# sx-fundec45-rev3.net
KiCad netlist of a schematic drawn in EAGLE
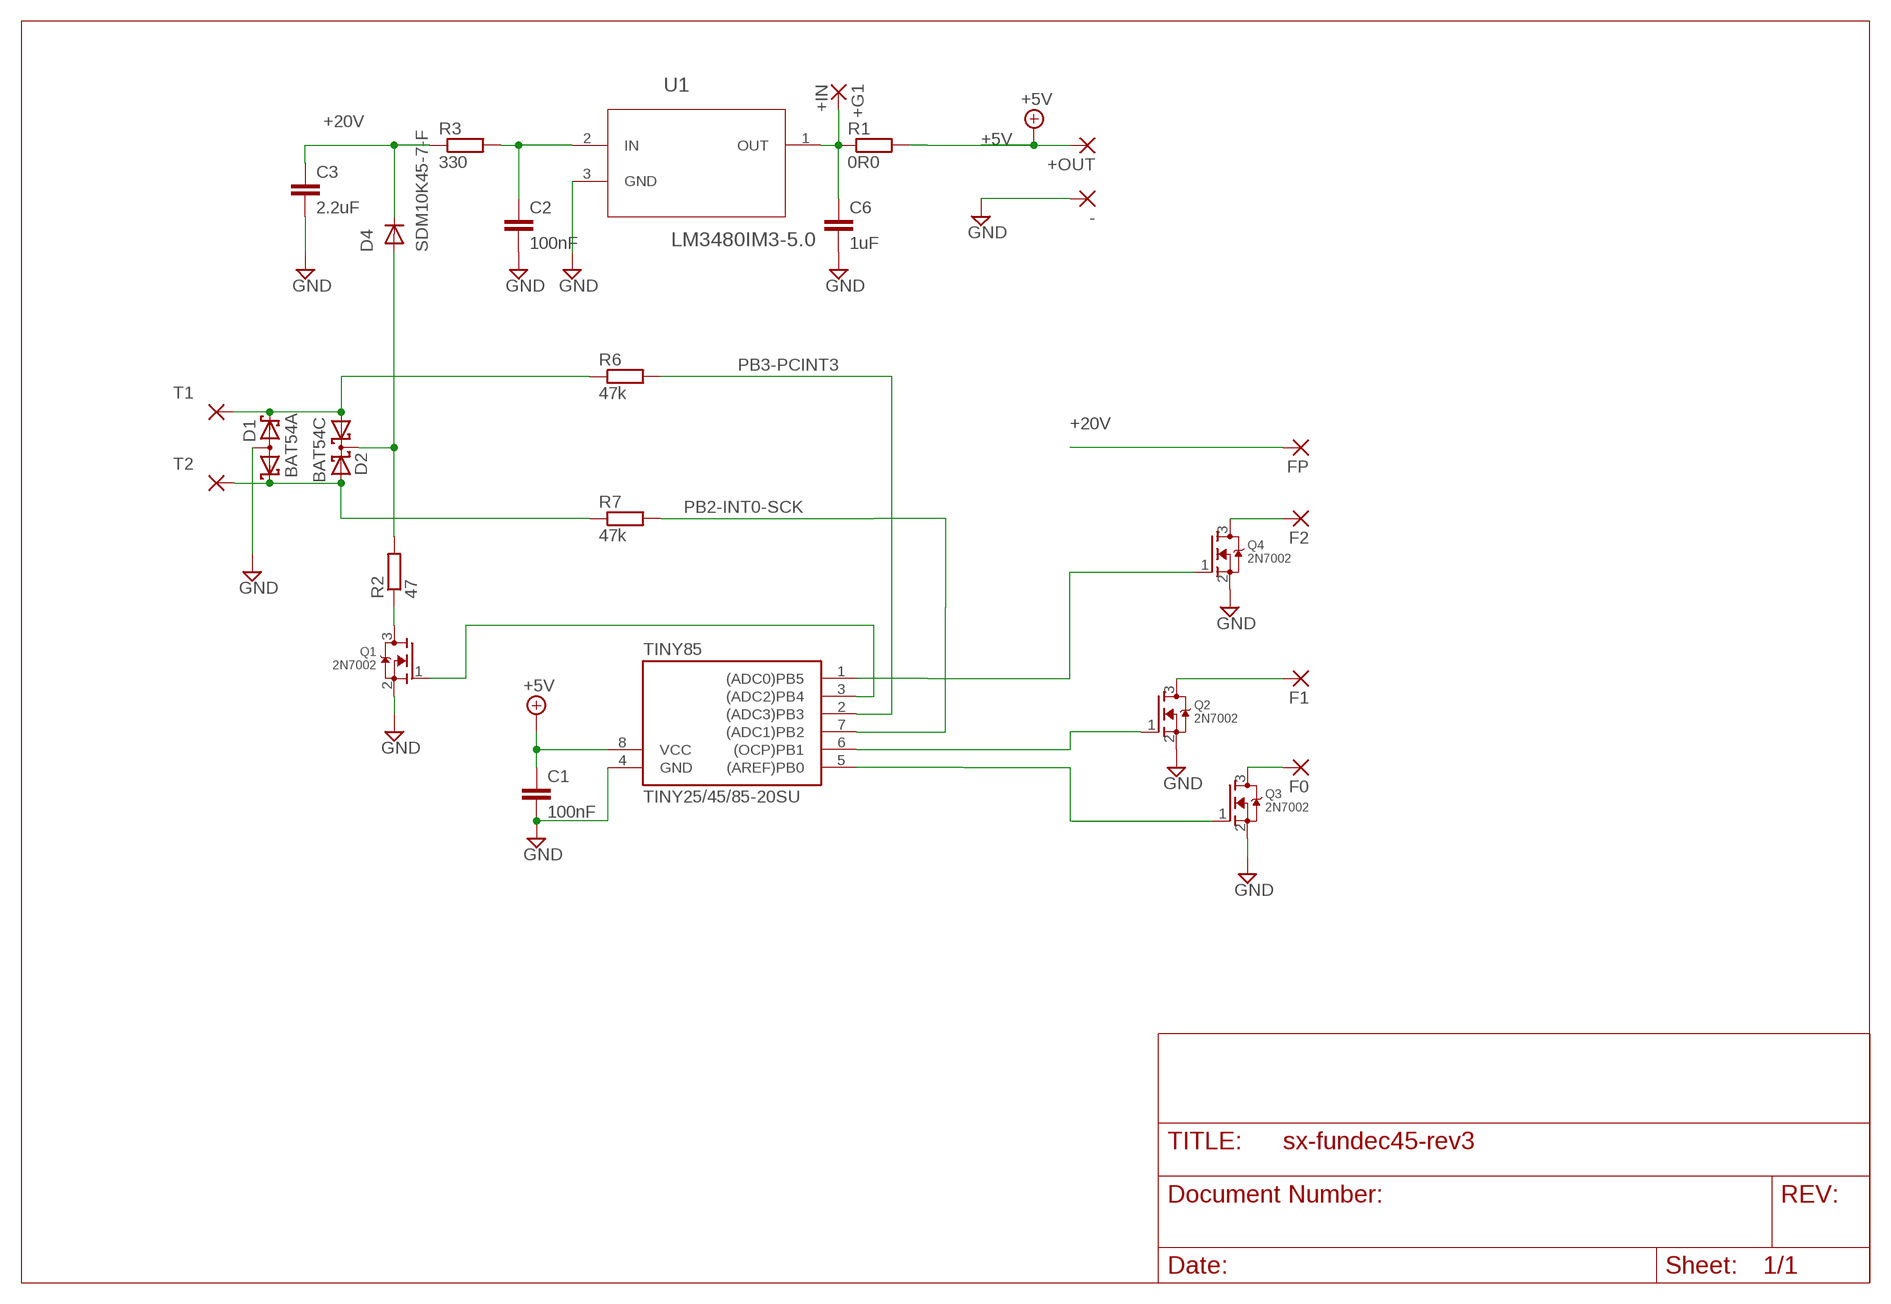
[diagram p0: schematic, sheet 1]

(export (version "E")
  (design (tool "Eeschema 10.0.6"))
  (components
    (comp (ref "+G1")
      (value "+IN")
      (footprint "eagle-import:SMD1,27-2,54")
      (libsource (lib "eagle-import") (part "SMD2"))
    )
    (comp (ref "+OUT")
      (value "SMD2")
      (footprint "eagle-import:SMD1,27-2,54")
      (libsource (lib "eagle-import") (part "SMD2"))
    )
    (comp (ref "-")
      (value "SMD2")
      (footprint "eagle-import:SMD1,27-2,54")
      (libsource (lib "eagle-import") (part "SMD2"))
    )
    (comp (ref "C1")
      (value "100nF")
      (footprint "eagle-import:C0805")
      (libsource (lib "eagle-import") (part "C-EUC0805"))
    )
    (comp (ref "C2")
      (value "100nF")
      (footprint "eagle-import:C0805")
      (libsource (lib "eagle-import") (part "C-EUC0805"))
    )
    (comp (ref "C3")
      (value "2.2uF")
      (footprint "eagle-import:C1206")
      (libsource (lib "eagle-import") (part "C-EUC1206"))
    )
    (comp (ref "C6")
      (value "1uF")
      (footprint "eagle-import:C0805")
      (libsource (lib "eagle-import") (part "C-EUC0805"))
    )
    (comp (ref "D1")
      (value "BAT54A")
      (footprint "eagle-import:SOT23")
      (libsource (lib "eagle-import") (part "BAT54A"))
    )
    (comp (ref "D2")
      (value "BAT54C")
      (footprint "eagle-import:SOT23")
      (libsource (lib "eagle-import") (part "BAT54C"))
    )
    (comp (ref "D4")
      (value "SDM10K45-7-F")
      (footprint "eagle-import:SOD323-R")
      (libsource (lib "eagle-import") (part "DIODE-SOD323-R"))
    )
    (comp (ref "F0")
      (value "SMD2")
      (footprint "eagle-import:SMD1,27-2,54")
      (libsource (lib "eagle-import") (part "SMD2"))
    )
    (comp (ref "F1")
      (value "SMD2")
      (footprint "eagle-import:SMD1,27-2,54")
      (libsource (lib "eagle-import") (part "SMD2"))
    )
    (comp (ref "F2")
      (value "SMD2")
      (footprint "eagle-import:SMD1,27-2,54")
      (libsource (lib "eagle-import") (part "SMD2"))
    )
    (comp (ref "FP")
      (value "SMD2")
      (footprint "eagle-import:SMD1,27-2,54")
      (libsource (lib "eagle-import") (part "SMD2"))
    )
    (comp (ref "Q1")
      (value "2N7002")
      (footprint "eagle-import:SOT23")
      (libsource (lib "eagle-import") (part "MOSFET-NREFLOW"))
    )
    (comp (ref "Q2")
      (value "2N7002")
      (footprint "eagle-import:SOT23")
      (libsource (lib "eagle-import") (part "MOSFET-NREFLOW"))
    )
    (comp (ref "Q3")
      (value "2N7002")
      (footprint "eagle-import:SOT23")
      (libsource (lib "eagle-import") (part "MOSFET-NREFLOW"))
    )
    (comp (ref "Q4")
      (value "2N7002")
      (footprint "eagle-import:SOT23")
      (libsource (lib "eagle-import") (part "MOSFET-NREFLOW"))
    )
    (comp (ref "R1")
      (value "0R0")
      (footprint "eagle-import:M0805")
      (libsource (lib "eagle-import") (part "R-EU_M0805"))
    )
    (comp (ref "R2")
      (value "47")
      (footprint "eagle-import:R0805")
      (libsource (lib "eagle-import") (part "R-EU_R0805"))
    )
    (comp (ref "R3")
      (value "330")
      (footprint "eagle-import:M0805")
      (libsource (lib "eagle-import") (part "R-EU_M0805"))
    )
    (comp (ref "R6")
      (value "47k")
      (footprint "eagle-import:R0805")
      (libsource (lib "eagle-import") (part "R-EU_R0805"))
    )
    (comp (ref "R7")
      (value "47k")
      (footprint "eagle-import:M0805")
      (libsource (lib "eagle-import") (part "R-EU_M0805"))
    )
    (comp (ref "T1")
      (value "SMD2")
      (footprint "eagle-import:SMD1,27-2,54")
      (libsource (lib "eagle-import") (part "SMD2"))
    )
    (comp (ref "T2")
      (value "SMD2")
      (footprint "eagle-import:SMD1,27-2,54")
      (libsource (lib "eagle-import") (part "SMD2"))
    )
    (comp (ref "TINY85")
      (value "TINY25/45/85-20SU")
      (footprint "eagle-import:SOIC8")
      (libsource (lib "eagle-import") (part "TINY25/45/85-20SU"))
    )
    (comp (ref "U1")
      (value "LM3480IM3-5.0")
      (footprint "eagle-import:SOT95P263X110-3N")
      (fields (field (name "MPN") "LM3480IM3-50"))
      (libsource (lib "eagle-import") (part "LM3480IM3-5.0"))
    )
  )
  (nets
    (net (code "1") (name "+5V") (class "Default")
      (node (ref "+OUT") (pin "1") (pinfunction "P_1") (pintype "passive"))
      (node (ref "C1") (pin "1") (pinfunction "1_1") (pintype "passive"))
      (node (ref "R1") (pin "2") (pinfunction "2_2") (pintype "passive"))
      (node (ref "TINY85") (pin "8") (pinfunction "VCC_8") (pintype "power_in"))
    )
    (net (code "2") (name "/+20V") (class "Default")
      (node (ref "C3") (pin "1") (pinfunction "1_1") (pintype "passive"))
      (node (ref "D4") (pin "C") (pinfunction "C_C") (pintype "passive"))
      (node (ref "FP") (pin "1") (pinfunction "P_1") (pintype "passive"))
      (node (ref "R3") (pin "1") (pinfunction "1_1") (pintype "passive"))
    )
    (net (code "3") (name "/PB2-INT0-SCK") (class "Default")
      (node (ref "R7") (pin "2") (pinfunction "2_2") (pintype "passive"))
      (node (ref "TINY85") (pin "7") (pinfunction "(ADC1)PB2_7") (pintype "bidirectional"))
    )
    (net (code "4") (name "/PB3-PCINT3") (class "Default")
      (node (ref "R6") (pin "2") (pinfunction "2_2") (pintype "passive"))
      (node (ref "TINY85") (pin "2") (pinfunction "(ADC3)PB3_2") (pintype "bidirectional"))
    )
    (net (code "5") (name "GND") (class "Default")
      (node (ref "-") (pin "1") (pinfunction "P_1") (pintype "passive"))
      (node (ref "C1") (pin "2") (pinfunction "2_2") (pintype "passive"))
      (node (ref "C2") (pin "2") (pinfunction "2_2") (pintype "passive"))
      (node (ref "C3") (pin "2") (pinfunction "2_2") (pintype "passive"))
      (node (ref "C6") (pin "2") (pinfunction "2_2") (pintype "passive"))
      (node (ref "D1") (pin "3") (pinfunction "AA_3") (pintype "passive"))
      (node (ref "Q1") (pin "2") (pinfunction "S_2") (pintype "bidirectional"))
      (node (ref "Q2") (pin "2") (pinfunction "S_2") (pintype "bidirectional"))
      (node (ref "Q3") (pin "2") (pinfunction "S_2") (pintype "bidirectional"))
      (node (ref "Q4") (pin "2") (pinfunction "S_2") (pintype "bidirectional"))
      (node (ref "TINY85") (pin "4") (pinfunction "GND_4") (pintype "power_in"))
      (node (ref "U1") (pin "3") (pinfunction "GND_3") (pintype "passive"))
    )
    (net (code "6") (name "Net-(+G1-P)") (class "Default")
      (node (ref "+G1") (pin "1") (pinfunction "P_1") (pintype "passive"))
      (node (ref "C6") (pin "1") (pinfunction "1_1") (pintype "passive"))
      (node (ref "R1") (pin "1") (pinfunction "1_1") (pintype "passive"))
      (node (ref "U1") (pin "1") (pinfunction "OUT_1") (pintype "output"))
    )
    (net (code "7") (name "Net-(D1-K1)") (class "Default")
      (node (ref "D1") (pin "1") (pinfunction "K1_1") (pintype "passive"))
      (node (ref "D2") (pin "2") (pinfunction "A2_2") (pintype "passive"))
      (node (ref "R7") (pin "1") (pinfunction "1_1") (pintype "passive"))
      (node (ref "T2") (pin "1") (pinfunction "P_1") (pintype "passive"))
    )
    (net (code "8") (name "Net-(D1-K2)") (class "Default")
      (node (ref "D1") (pin "2") (pinfunction "K2_2") (pintype "passive"))
      (node (ref "D2") (pin "1") (pinfunction "A1_1") (pintype "passive"))
      (node (ref "R6") (pin "1") (pinfunction "1_1") (pintype "passive"))
      (node (ref "T1") (pin "1") (pinfunction "P_1") (pintype "passive"))
    )
    (net (code "9") (name "Net-(D2-CC)") (class "Default")
      (node (ref "D2") (pin "3") (pinfunction "CC_3") (pintype "passive"))
      (node (ref "D4") (pin "A") (pinfunction "A_A") (pintype "passive"))
      (node (ref "R2") (pin "2") (pinfunction "2_2") (pintype "passive"))
    )
    (net (code "10") (name "Net-(F0-P)") (class "Default")
      (node (ref "F0") (pin "1") (pinfunction "P_1") (pintype "passive"))
      (node (ref "Q3") (pin "3") (pinfunction "D_3") (pintype "bidirectional"))
    )
    (net (code "11") (name "Net-(F1-P)") (class "Default")
      (node (ref "F1") (pin "1") (pinfunction "P_1") (pintype "passive"))
      (node (ref "Q2") (pin "3") (pinfunction "D_3") (pintype "bidirectional"))
    )
    (net (code "12") (name "Net-(F2-P)") (class "Default")
      (node (ref "F2") (pin "1") (pinfunction "P_1") (pintype "passive"))
      (node (ref "Q4") (pin "3") (pinfunction "D_3") (pintype "bidirectional"))
    )
    (net (code "13") (name "Net-(Q1-D)") (class "Default")
      (node (ref "Q1") (pin "3") (pinfunction "D_3") (pintype "bidirectional"))
      (node (ref "R2") (pin "1") (pinfunction "1_1") (pintype "passive"))
    )
    (net (code "14") (name "Net-(Q1-G)") (class "Default")
      (node (ref "Q1") (pin "1") (pinfunction "G_1") (pintype "bidirectional"))
      (node (ref "TINY85") (pin "3") (pinfunction "(ADC2)PB4_3") (pintype "bidirectional"))
    )
    (net (code "15") (name "Net-(Q2-G)") (class "Default")
      (node (ref "Q2") (pin "1") (pinfunction "G_1") (pintype "bidirectional"))
      (node (ref "TINY85") (pin "6") (pinfunction "(OCP)PB1_6") (pintype "bidirectional"))
    )
    (net (code "16") (name "Net-(Q3-G)") (class "Default")
      (node (ref "Q3") (pin "1") (pinfunction "G_1") (pintype "bidirectional"))
      (node (ref "TINY85") (pin "5") (pinfunction "(AREF)PB0_5") (pintype "bidirectional"))
    )
    (net (code "17") (name "Net-(Q4-G)") (class "Default")
      (node (ref "Q4") (pin "1") (pinfunction "G_1") (pintype "bidirectional"))
      (node (ref "TINY85") (pin "1") (pinfunction "(ADC0)PB5_1") (pintype "bidirectional"))
    )
    (net (code "18") (name "Net-(U1-IN)") (class "Default")
      (node (ref "C2") (pin "1") (pinfunction "1_1") (pintype "passive"))
      (node (ref "R3") (pin "2") (pinfunction "2_2") (pintype "passive"))
      (node (ref "U1") (pin "2") (pinfunction "IN_2") (pintype "power_in"))
    )
  )
)
